# main.net
KiCad netlist of a schematic drawn in Altium Designer
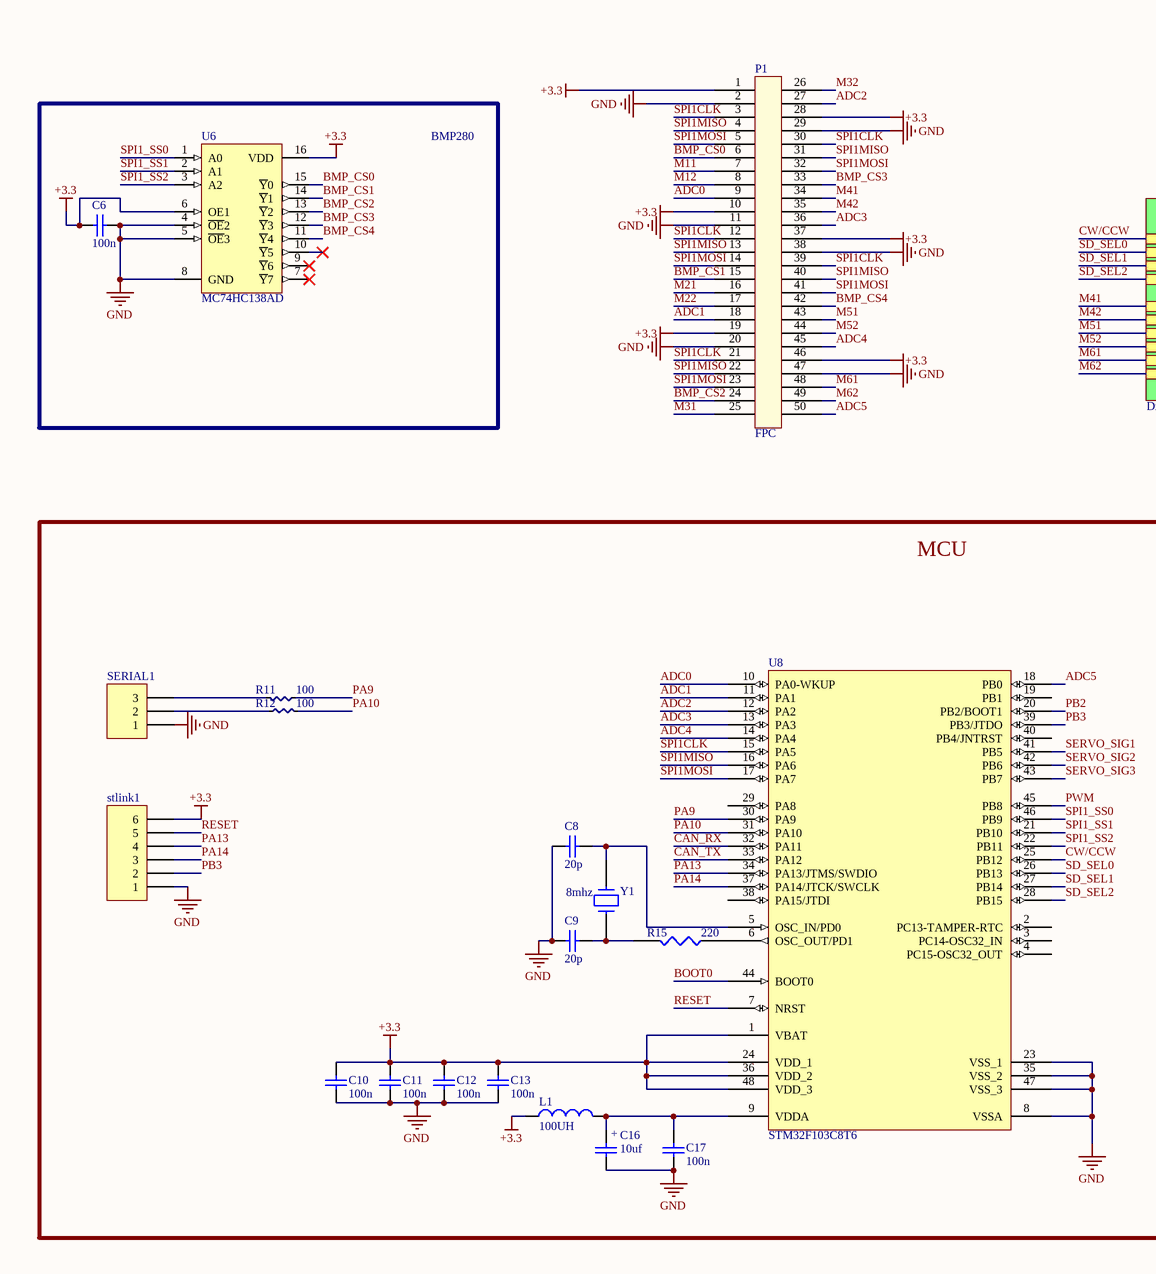
[diagram p0: main.SchDoc, left]
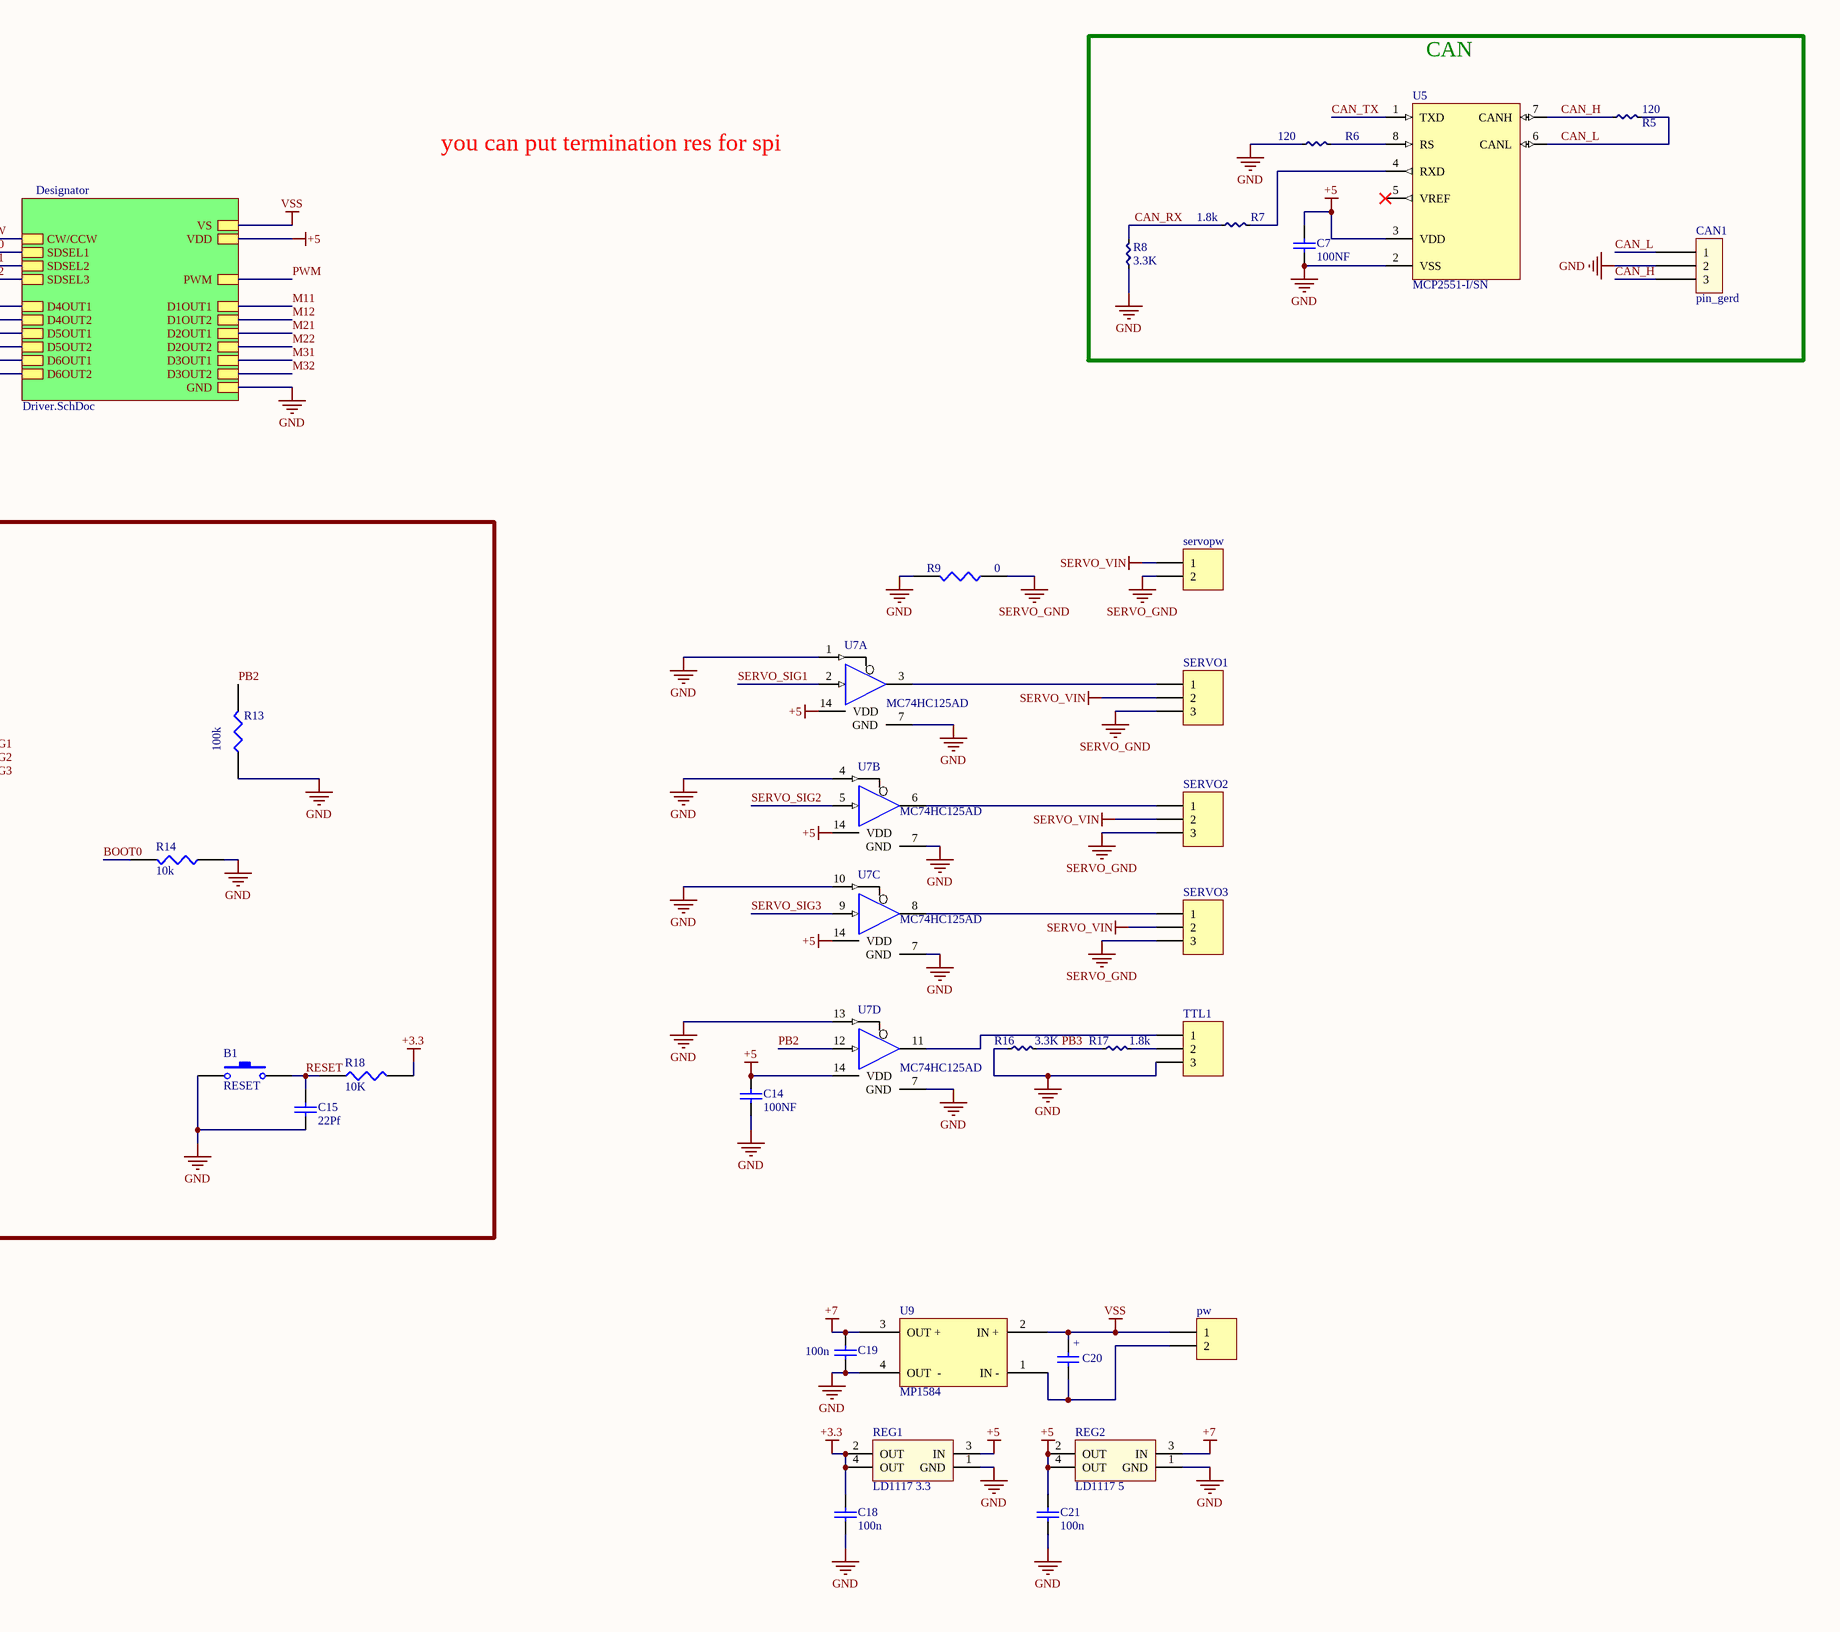
[diagram p1: main.SchDoc, right]

(export (version "E")
  (design (tool "Eeschema 10.0.6"))
  (components
    (comp (ref "B1")
      (value "RESET")
      (footprint "SMD PUSH BUTTON")
      (libsource (lib "AMINLIB") (part "SMD_PUSH_BUTTON"))
    )
    (comp (ref "C6")
      (value "100n")
      (footprint "MY_CAP_SMD_0805")
      (libsource (lib "AMINLIB") (part "CAP SMD"))
    )
    (comp (ref "C7")
      (value "100NF")
      (footprint "MY_CAP_SMD_0805")
      (description "2.0 mm × 1.25 mm")
      (libsource (lib "AMINLIB") (part "CAP SMD_0805"))
    )
    (comp (ref "C8") (value "20p") (footprint "MY_CAP_SMD_0805") (libsource (lib "AMINLIB") (part "CAP SMD")))
    (comp (ref "C9") (value "20p") (footprint "MY_CAP_SMD_0805") (libsource (lib "AMINLIB") (part "CAP SMD")))
    (comp (ref "C10")
      (value "100n")
      (footprint "MY_CAP_SMD_0805")
      (libsource (lib "AMINLIB") (part "CAP SMD"))
    )
    (comp (ref "C11")
      (value "100n")
      (footprint "MY_CAP_SMD_0805")
      (libsource (lib "AMINLIB") (part "CAP SMD"))
    )
    (comp (ref "C12")
      (value "100n")
      (footprint "MY_CAP_SMD_0805")
      (libsource (lib "AMINLIB") (part "CAP SMD"))
    )
    (comp (ref "C13")
      (value "100n")
      (footprint "MY_CAP_SMD_0805")
      (libsource (lib "AMINLIB") (part "CAP SMD"))
    )
    (comp (ref "C14")
      (value "100NF")
      (footprint "MY_CAP_SMD_0805")
      (description "2.0 mm × 1.25 mm")
      (libsource (lib "AMINLIB") (part "CAP SMD_0805"))
    )
    (comp (ref "C15")
      (value "22Pf")
      (footprint "MY_CAP_SMD_0805")
      (libsource (lib "AMINLIB") (part "CAP SMD"))
    )
    (comp (ref "C16")
      (value "10uf")
      (footprint "MY_cap_smd10uf")
      (libsource (lib "AMINLIB") (part "cap_smd_10u"))
    )
    (comp (ref "C17")
      (value "100n")
      (footprint "MY_CAP_SMD_0805")
      (libsource (lib "AMINLIB") (part "CAP SMD"))
    )
    (comp (ref "C18")
      (value "100n")
      (footprint "MY_CAP_SMD_0805")
      (libsource (lib "AMINLIB") (part "CAP SMD"))
    )
    (comp (ref "C19")
      (value "100n")
      (footprint "MY_CAP_SMD_0805")
      (libsource (lib "AMINLIB") (part "CAP SMD"))
    )
    (comp (ref "C20")
      (value "Cap")
      (footprint "MY_CAP_SMD-C")
      (description "6X3.2MM")
      (libsource (lib "AMINLIB") (part "CAP_TANTAL_C"))
    )
    (comp (ref "C21")
      (value "100n")
      (footprint "MY_CAP_SMD_0805")
      (libsource (lib "AMINLIB") (part "CAP SMD"))
    )
    (comp (ref "CAN1")
      (value "pin_gerd")
      (footprint "MY_PINGERD3")
      (description "3pin")
      (libsource (lib "AMINLIB") (part "pin_gerd"))
    )
    (comp (ref "L1")
      (value "100UH")
      (footprint "MY_SMD_INDUCTOR")
      (libsource (lib "AMINLIB") (part "INDUCTOR SMD"))
    )
    (comp (ref "P1")
      (value "FPC")
      (footprint "FPC-50-POS-0.5-MM")
      (libsource (lib "HAND-MULTILAYER") (part "FPC-50-POS-0.5-MM"))
    )
    (comp (ref "pw")
      (value "Header 2")
      (footprint "My_1X02")
      (description "Header, 2-Pin")
      (fields (field (name "PUBLISHER") "Altium Limited"))
      (libsource (lib "AMINLIB") (part "Header 2"))
    )
    (comp (ref "R5")
      (value "120")
      (footprint "MY_RES_SMD_0805")
      (libsource (lib "AMINLIB") (part "RES SMD 0805"))
    )
    (comp (ref "R6")
      (value "120")
      (footprint "MY_RES_SMD_0805")
      (libsource (lib "AMINLIB") (part "RES SMD 0805"))
    )
    (comp (ref "R7")
      (value "1.8k")
      (footprint "MY_RES_SMD_0805")
      (libsource (lib "AMINLIB") (part "RES SMD 0805"))
    )
    (comp (ref "R8")
      (value "3.3K")
      (footprint "MY_RES_SMD_0805")
      (libsource (lib "AMINLIB") (part "RES SMD 0805"))
    )
    (comp (ref "R9") (value "0") (footprint "MY_RES_SMD_0805") (libsource (lib "AMINLIB") (part "RES SMD")))
    (comp (ref "R11")
      (value "100")
      (footprint "MY_RES_SMD_0805")
      (libsource (lib "AMINLIB") (part "RES SMD 0805"))
    )
    (comp (ref "R12")
      (value "100")
      (footprint "MY_RES_SMD_0805")
      (libsource (lib "AMINLIB") (part "RES SMD 0805"))
    )
    (comp (ref "R13")
      (value "100k")
      (footprint "MY_RES_SMD_0805")
      (libsource (lib "AMINLIB") (part "RES SMD"))
    )
    (comp (ref "R14")
      (value "10k")
      (footprint "MY_RES_SMD_0805")
      (libsource (lib "AMINLIB") (part "RES SMD"))
    )
    (comp (ref "R15")
      (value "220")
      (footprint "MY_RES_SMD_0805")
      (libsource (lib "AMINLIB") (part "RES SMD"))
    )
    (comp (ref "R16")
      (value "3.3K")
      (footprint "MY_RES_SMD_0805")
      (libsource (lib "AMINLIB") (part "RES SMD 0805"))
    )
    (comp (ref "R17")
      (value "1.8k")
      (footprint "MY_RES_SMD_0805")
      (libsource (lib "AMINLIB") (part "RES SMD 0805"))
    )
    (comp (ref "R18")
      (value "10K")
      (footprint "MY_RES_SMD_0805")
      (libsource (lib "AMINLIB") (part "RES SMD"))
    )
    (comp (ref "REG1")
      (value "LD1117 3.3")
      (footprint "MY_LD1117-3.3")
      (libsource (lib "AMINLIB") (part "LD1117 3.3"))
    )
    (comp (ref "REG2")
      (value "LD1117 5")
      (footprint "MY_LD1117-3.3")
      (libsource (lib "AMINLIB") (part "LD1117 3.3"))
    )
    (comp (ref "SERIAL1")
      (value "Header 3")
      (footprint "My_1X03")
      (description "Header, 3-Pin")
      (fields (field (name "PUBLISHER") "Altium Limited"))
      (libsource (lib "") (part "Header 3_1"))
    )
    (comp (ref "SERVO1")
      (value "Header 3")
      (footprint "My_1X03")
      (description "Header, 3-Pin")
      (fields (field (name "PUBLISHER") "Altium Limited"))
      (libsource (lib "AMINLIB") (part "Header 3"))
    )
    (comp (ref "SERVO2")
      (value "Header 3")
      (footprint "My_1X03")
      (description "Header, 3-Pin")
      (fields (field (name "PUBLISHER") "Altium Limited"))
      (libsource (lib "AMINLIB") (part "Header 3"))
    )
    (comp (ref "SERVO3")
      (value "Header 3")
      (footprint "My_1X03")
      (description "Header, 3-Pin")
      (fields (field (name "PUBLISHER") "Altium Limited"))
      (libsource (lib "AMINLIB") (part "Header 3"))
    )
    (comp (ref "servopw")
      (value "Header 2")
      (footprint "My_1X02")
      (description "Header, 2-Pin")
      (fields (field (name "PUBLISHER") "Altium Limited"))
      (libsource (lib "AMINLIB") (part "Header 2"))
    )
    (comp (ref "stlink1")
      (value "Header 6")
      (footprint "My_1X06")
      (description "Header, 6-Pin")
      (fields (field (name "PUBLISHER") "Altium Limited"))
      (libsource (lib "AMINLIB") (part "Header 6"))
    )
    (comp (ref "TTL1")
      (value "Header 3")
      (footprint "My_1X03")
      (description "Header, 3-Pin")
      (fields (field (name "PUBLISHER") "Altium Limited"))
      (libsource (lib "AMINLIB") (part "Header 3"))
    )
    (comp (ref "U5")
      (value "MCP2551-I/SN")
      (footprint "SOIC-SN8_N")
      (description "High-Speed CAN Transceiver, 8-Pin SOIC, Industrial Temperature")
      (fields (field (name "PUBLISHER") "Altium Limited"))
      (libsource (lib "Microchip Interface") (part "MCP2551-I/SN"))
    )
    (comp (ref "U6")
      (value "MC74HC138AD")
      (footprint "751B-03_N")
      (description "1-of-8 Decoder/Demultiplexer")
      (fields (field (name "PUBLISHER") "Altium Limited"))
      (libsource (lib "Motorola Logic Decoder Demux") (part "MC74HC138AD"))
    )
    (comp (ref "U7")
      (value "MC74HC125AD")
      (footprint "751A-02_N")
      (description "Quad 3-State Non-Inverting Buffer")
      (fields (field (name "PUBLISHER") "Altium Limited"))
      (libsource (lib "Motorola Logic Buffer Line Driver") (part "MC74HC125AD"))
    )
    (comp (ref "U8")
      (value "STM32F103C8T6")
      (footprint "LQFP48_N")
      (description "STM32 ARM-based 32-bit MCU with 64 Kbytes Flash, 48-pin LQFP, Industrial Temperature")
      (fields (field (name "PUBLISHER") "Altium Limited"))
      (libsource (lib "ST Microcontroller 32-Bit STM32") (part "STM32F103C8T6"))
    )
    (comp (ref "U9")
      (value "MP1584")
      (footprint "mp1584")
      (description "SWITCHING REGULATOR MODULE")
      (fields (field (name "PART") "MP1584EN-LF-Z"))
      (libsource (lib "AMINLIB") (part "MP1584"))
    )
    (comp (ref "Y1")
      (value "8mhz")
      (footprint "My_Crystal - SMD")
      (description "Crystal")
      (libsource (lib "AMINLIB") (part "CRYSTAL"))
    )
  )
  (nets
    (net (code "1") (name "+3.3") (class "Default")
      (node (ref "C10") (pin "2") (pinfunction "2_2") (pintype "passive"))
      (node (ref "C11") (pin "2") (pinfunction "2_2") (pintype "passive"))
      (node (ref "C12") (pin "2") (pinfunction "2_2") (pintype "passive"))
      (node (ref "C13") (pin "2") (pinfunction "2_2") (pintype "passive"))
      (node (ref "C18") (pin "2") (pinfunction "2_2") (pintype "passive"))
      (node (ref "C6") (pin "2") (pinfunction "2_2") (pintype "passive"))
      (node (ref "L1") (pin "1") (pinfunction "1_1") (pintype "passive"))
      (node (ref "P1") (pin "1") (pinfunction "1_1") (pintype "passive"))
      (node (ref "P1") (pin "10") (pinfunction "10_10") (pintype "passive"))
      (node (ref "P1") (pin "19") (pinfunction "19_19") (pintype "passive"))
      (node (ref "P1") (pin "28") (pinfunction "28_28") (pintype "passive"))
      (node (ref "P1") (pin "37") (pinfunction "37_37") (pintype "passive"))
      (node (ref "P1") (pin "46") (pinfunction "46_46") (pintype "passive"))
      (node (ref "R18") (pin "2") (pinfunction "2_2") (pintype "passive"))
      (node (ref "REG1") (pin "2") (pinfunction "OUT_2") (pintype "power_in"))
      (node (ref "REG1") (pin "4") (pinfunction "OUT_4") (pintype "power_in"))
      (node (ref "U6") (pin "16") (pinfunction "VDD_16") (pintype "power_in"))
      (node (ref "U6") (pin "6") (pinfunction "OE1_6") (pintype "input"))
      (node (ref "U8") (pin "1") (pinfunction "VBAT_1") (pintype "power_in"))
      (node (ref "U8") (pin "24") (pinfunction "VDD_1_24") (pintype "power_in"))
      (node (ref "U8") (pin "36") (pinfunction "VDD_2_36") (pintype "power_in"))
      (node (ref "U8") (pin "48") (pinfunction "VDD_3_48") (pintype "power_in"))
      (node (ref "stlink1") (pin "6") (pinfunction "6_6") (pintype "passive"))
    )
    (net (code "2") (name "+5") (class "Default")
      (node (ref "C14") (pin "2") (pinfunction "2_2") (pintype "passive"))
      (node (ref "C21") (pin "2") (pinfunction "2_2") (pintype "passive"))
      (node (ref "C7") (pin "2") (pinfunction "2_2") (pintype "passive"))
      (node (ref "REG1") (pin "3") (pinfunction "IN_3") (pintype "power_in"))
      (node (ref "REG2") (pin "2") (pinfunction "OUT_2") (pintype "power_in"))
      (node (ref "REG2") (pin "4") (pinfunction "OUT_4") (pintype "power_in"))
      (node (ref "U5") (pin "3") (pinfunction "VDD_3") (pintype "power_in"))
      (node (ref "U7") (pin "14") (pinfunction "VDD_14") (pintype "power_in"))
    )
    (net (code "3") (name "+7") (class "Default")
      (node (ref "C19") (pin "2") (pinfunction "2_2") (pintype "passive"))
      (node (ref "REG2") (pin "3") (pinfunction "IN_3") (pintype "power_in"))
      (node (ref "U9") (pin "3") (pinfunction "OUT_+_3") (pintype "passive"))
    )
    (net (code "4") (name "/ADC0") (class "Default")
      (node (ref "P1") (pin "9") (pinfunction "9_9") (pintype "passive"))
      (node (ref "U8") (pin "10") (pinfunction "PA0-WKUP_10") (pintype "bidirectional"))
    )
    (net (code "5") (name "/ADC1") (class "Default")
      (node (ref "P1") (pin "18") (pinfunction "18_18") (pintype "passive"))
      (node (ref "U8") (pin "11") (pinfunction "PA1_11") (pintype "bidirectional"))
    )
    (net (code "6") (name "/ADC2") (class "Default")
      (node (ref "P1") (pin "27") (pinfunction "27_27") (pintype "passive"))
      (node (ref "U8") (pin "12") (pinfunction "PA2_12") (pintype "bidirectional"))
    )
    (net (code "7") (name "/ADC3") (class "Default")
      (node (ref "P1") (pin "36") (pinfunction "36_36") (pintype "passive"))
      (node (ref "U8") (pin "13") (pinfunction "PA3_13") (pintype "bidirectional"))
    )
    (net (code "8") (name "/ADC4") (class "Default")
      (node (ref "P1") (pin "45") (pinfunction "45_45") (pintype "passive"))
      (node (ref "U8") (pin "14") (pinfunction "PA4_14") (pintype "bidirectional"))
    )
    (net (code "9") (name "/ADC5") (class "Default")
      (node (ref "P1") (pin "50") (pinfunction "50_50") (pintype "passive"))
      (node (ref "U8") (pin "18") (pinfunction "PB0_18") (pintype "bidirectional"))
    )
    (net (code "10") (name "/BMP_CS0") (class "Default")
      (node (ref "P1") (pin "6") (pinfunction "6_6") (pintype "passive"))
      (node (ref "U6") (pin "15") (pinfunction "~{Y}0_15") (pintype "output"))
    )
    (net (code "11") (name "/BMP_CS1") (class "Default")
      (node (ref "P1") (pin "15") (pinfunction "15_15") (pintype "passive"))
      (node (ref "U6") (pin "14") (pinfunction "~{Y}1_14") (pintype "output"))
    )
    (net (code "12") (name "/BMP_CS2") (class "Default")
      (node (ref "P1") (pin "24") (pinfunction "24_24") (pintype "passive"))
      (node (ref "U6") (pin "13") (pinfunction "~{Y}2_13") (pintype "output"))
    )
    (net (code "13") (name "/BMP_CS3") (class "Default")
      (node (ref "P1") (pin "33") (pinfunction "33_33") (pintype "passive"))
      (node (ref "U6") (pin "12") (pinfunction "~{Y}3_12") (pintype "output"))
    )
    (net (code "14") (name "/BMP_CS4") (class "Default")
      (node (ref "P1") (pin "42") (pinfunction "42_42") (pintype "passive"))
      (node (ref "U6") (pin "11") (pinfunction "~{Y}4_11") (pintype "output"))
    )
    (net (code "15") (name "/BOOT0") (class "Default")
      (node (ref "R14") (pin "2") (pinfunction "2_2") (pintype "passive"))
      (node (ref "U8") (pin "44") (pinfunction "BOOT0_44") (pintype "input"))
    )
    (net (code "16") (name "/CAN_H") (class "Default")
      (node (ref "CAN1") (pin "3") (pinfunction "3_3") (pintype "passive"))
      (node (ref "R5") (pin "1") (pinfunction "1_1") (pintype "passive"))
      (node (ref "U5") (pin "7") (pinfunction "CANH_7") (pintype "bidirectional"))
    )
    (net (code "17") (name "/CAN_L") (class "Default")
      (node (ref "CAN1") (pin "1") (pinfunction "1_1") (pintype "passive"))
      (node (ref "R5") (pin "2") (pinfunction "2_2") (pintype "passive"))
      (node (ref "U5") (pin "6") (pinfunction "CANL_6") (pintype "bidirectional"))
    )
    (net (code "18") (name "/CAN_RX") (class "Default")
      (node (ref "R7") (pin "1") (pinfunction "1_1") (pintype "passive"))
      (node (ref "R8") (pin "2") (pinfunction "2_2") (pintype "passive"))
      (node (ref "U8") (pin "32") (pinfunction "PA11_32") (pintype "bidirectional"))
    )
    (net (code "19") (name "/CAN_TX") (class "Default")
      (node (ref "U5") (pin "1") (pinfunction "TXD_1") (pintype "input"))
      (node (ref "U8") (pin "33") (pinfunction "PA12_33") (pintype "bidirectional"))
    )
    (net (code "20") (name "/CW{slash}CCW") (class "Default")
      (node (ref "U8") (pin "25") (pinfunction "PB12_25") (pintype "bidirectional"))
    )
    (net (code "21") (name "/M11") (class "Default")
      (node (ref "P1") (pin "7") (pinfunction "7_7") (pintype "passive"))
    )
    (net (code "22") (name "/M12") (class "Default")
      (node (ref "P1") (pin "8") (pinfunction "8_8") (pintype "passive"))
    )
    (net (code "23") (name "/M21") (class "Default")
      (node (ref "P1") (pin "16") (pinfunction "16_16") (pintype "passive"))
    )
    (net (code "24") (name "/M22") (class "Default")
      (node (ref "P1") (pin "17") (pinfunction "17_17") (pintype "passive"))
    )
    (net (code "25") (name "/M31") (class "Default")
      (node (ref "P1") (pin "25") (pinfunction "25_25") (pintype "passive"))
    )
    (net (code "26") (name "/M32") (class "Default")
      (node (ref "P1") (pin "26") (pinfunction "26_26") (pintype "passive"))
    )
    (net (code "27") (name "/M41") (class "Default")
      (node (ref "P1") (pin "34") (pinfunction "34_34") (pintype "passive"))
    )
    (net (code "28") (name "/M42") (class "Default")
      (node (ref "P1") (pin "35") (pinfunction "35_35") (pintype "passive"))
    )
    (net (code "29") (name "/M51") (class "Default")
      (node (ref "P1") (pin "43") (pinfunction "43_43") (pintype "passive"))
    )
    (net (code "30") (name "/M52") (class "Default")
      (node (ref "P1") (pin "44") (pinfunction "44_44") (pintype "passive"))
    )
    (net (code "31") (name "/M61") (class "Default")
      (node (ref "P1") (pin "48") (pinfunction "48_48") (pintype "passive"))
    )
    (net (code "32") (name "/M62") (class "Default")
      (node (ref "P1") (pin "49") (pinfunction "49_49") (pintype "passive"))
    )
    (net (code "33") (name "/PA9") (class "Default")
      (node (ref "R11") (pin "1") (pinfunction "1_1") (pintype "passive"))
      (node (ref "U8") (pin "30") (pinfunction "PA9_30") (pintype "bidirectional"))
    )
    (net (code "34") (name "/PA10") (class "Default")
      (node (ref "R12") (pin "2") (pinfunction "2_2") (pintype "passive"))
      (node (ref "U8") (pin "31") (pinfunction "PA10_31") (pintype "bidirectional"))
    )
    (net (code "35") (name "/PA13") (class "Default")
      (node (ref "U8") (pin "34") (pinfunction "PA13/JTMS/SWDIO_34") (pintype "bidirectional"))
      (node (ref "stlink1") (pin "4") (pinfunction "4_4") (pintype "passive"))
    )
    (net (code "36") (name "/PA14") (class "Default")
      (node (ref "U8") (pin "37") (pinfunction "PA14/JTCK/SWCLK_37") (pintype "bidirectional"))
      (node (ref "stlink1") (pin "3") (pinfunction "3_3") (pintype "passive"))
    )
    (net (code "37") (name "/PB2") (class "Default")
      (node (ref "R13") (pin "2") (pinfunction "2_2") (pintype "passive"))
      (node (ref "U7") (pin "12") (pinfunction "A_12") (pintype "input"))
      (node (ref "U8") (pin "20") (pinfunction "PB2/BOOT1_20") (pintype "bidirectional"))
    )
    (net (code "38") (name "/PB3") (class "Default")
      (node (ref "R16") (pin "2") (pinfunction "2_2") (pintype "passive"))
      (node (ref "R17") (pin "1") (pinfunction "1_1") (pintype "passive"))
      (node (ref "U8") (pin "39") (pinfunction "PB3/JTDO_39") (pintype "bidirectional"))
      (node (ref "stlink1") (pin "2") (pinfunction "2_2") (pintype "passive"))
    )
    (net (code "39") (name "/PWM") (class "Default")
      (node (ref "U8") (pin "45") (pinfunction "PB8_45") (pintype "bidirectional"))
    )
    (net (code "40") (name "/RESET") (class "Default")
      (node (ref "B1") (pin "2") (pinfunction "2_2") (pintype "passive"))
      (node (ref "C15") (pin "2") (pinfunction "2_2") (pintype "passive"))
      (node (ref "R18") (pin "1") (pinfunction "1_1") (pintype "passive"))
      (node (ref "U8") (pin "7") (pinfunction "NRST_7") (pintype "bidirectional"))
      (node (ref "stlink1") (pin "5") (pinfunction "5_5") (pintype "passive"))
    )
    (net (code "41") (name "/SD_SEL0") (class "Default")
      (node (ref "U8") (pin "26") (pinfunction "PB13_26") (pintype "bidirectional"))
    )
    (net (code "42") (name "/SD_SEL1") (class "Default")
      (node (ref "U8") (pin "27") (pinfunction "PB14_27") (pintype "bidirectional"))
    )
    (net (code "43") (name "/SD_SEL2") (class "Default")
      (node (ref "U8") (pin "28") (pinfunction "PB15_28") (pintype "bidirectional"))
    )
    (net (code "44") (name "/SERVO_SIG1") (class "Default")
      (node (ref "U7") (pin "2") (pinfunction "A_2") (pintype "input"))
      (node (ref "U8") (pin "41") (pinfunction "PB5_41") (pintype "bidirectional"))
    )
    (net (code "45") (name "/SERVO_SIG2") (class "Default")
      (node (ref "U7") (pin "5") (pinfunction "A_5") (pintype "input"))
      (node (ref "U8") (pin "42") (pinfunction "PB6_42") (pintype "bidirectional"))
    )
    (net (code "46") (name "/SERVO_SIG3") (class "Default")
      (node (ref "U7") (pin "9") (pinfunction "A_9") (pintype "input"))
      (node (ref "U8") (pin "43") (pinfunction "PB7_43") (pintype "bidirectional"))
    )
    (net (code "47") (name "/SPI1CLK") (class "Default")
      (node (ref "P1") (pin "12") (pinfunction "12_12") (pintype "passive"))
      (node (ref "P1") (pin "21") (pinfunction "21_21") (pintype "passive"))
      (node (ref "P1") (pin "3") (pinfunction "3_3") (pintype "passive"))
      (node (ref "P1") (pin "30") (pinfunction "30_30") (pintype "passive"))
      (node (ref "P1") (pin "39") (pinfunction "39_39") (pintype "passive"))
      (node (ref "U8") (pin "15") (pinfunction "PA5_15") (pintype "bidirectional"))
    )
    (net (code "48") (name "/SPI1MISO") (class "Default")
      (node (ref "P1") (pin "13") (pinfunction "13_13") (pintype "passive"))
      (node (ref "P1") (pin "22") (pinfunction "22_22") (pintype "passive"))
      (node (ref "P1") (pin "31") (pinfunction "31_31") (pintype "passive"))
      (node (ref "P1") (pin "4") (pinfunction "4_4") (pintype "passive"))
      (node (ref "P1") (pin "40") (pinfunction "40_40") (pintype "passive"))
      (node (ref "U8") (pin "16") (pinfunction "PA6_16") (pintype "bidirectional"))
    )
    (net (code "49") (name "/SPI1MOSI") (class "Default")
      (node (ref "P1") (pin "14") (pinfunction "14_14") (pintype "passive"))
      (node (ref "P1") (pin "23") (pinfunction "23_23") (pintype "passive"))
      (node (ref "P1") (pin "32") (pinfunction "32_32") (pintype "passive"))
      (node (ref "P1") (pin "41") (pinfunction "41_41") (pintype "passive"))
      (node (ref "P1") (pin "5") (pinfunction "5_5") (pintype "passive"))
      (node (ref "U8") (pin "17") (pinfunction "PA7_17") (pintype "bidirectional"))
    )
    (net (code "50") (name "/SPI1_SS0") (class "Default")
      (node (ref "U6") (pin "1") (pinfunction "A0_1") (pintype "input"))
      (node (ref "U8") (pin "46") (pinfunction "PB9_46") (pintype "bidirectional"))
    )
    (net (code "51") (name "/SPI1_SS1") (class "Default")
      (node (ref "U6") (pin "2") (pinfunction "A1_2") (pintype "input"))
      (node (ref "U8") (pin "21") (pinfunction "PB10_21") (pintype "bidirectional"))
    )
    (net (code "52") (name "/SPI1_SS2") (class "Default")
      (node (ref "U6") (pin "3") (pinfunction "A2_3") (pintype "input"))
      (node (ref "U8") (pin "22") (pinfunction "PB11_22") (pintype "bidirectional"))
    )
    (net (code "53") (name "GND") (class "Default")
      (node (ref "B1") (pin "1") (pinfunction "1_1") (pintype "passive"))
      (node (ref "C10") (pin "1") (pinfunction "1_1") (pintype "passive"))
      (node (ref "C11") (pin "1") (pinfunction "1_1") (pintype "passive"))
      (node (ref "C12") (pin "1") (pinfunction "1_1") (pintype "passive"))
      (node (ref "C13") (pin "1") (pinfunction "1_1") (pintype "passive"))
      (node (ref "C14") (pin "1") (pinfunction "1_1") (pintype "passive"))
      (node (ref "C15") (pin "1") (pinfunction "1_1") (pintype "passive"))
      (node (ref "C16") (pin "-") (pinfunction "-_-") (pintype "passive"))
      (node (ref "C17") (pin "1") (pinfunction "1_1") (pintype "passive"))
      (node (ref "C18") (pin "1") (pinfunction "1_1") (pintype "passive"))
      (node (ref "C19") (pin "1") (pinfunction "1_1") (pintype "passive"))
      (node (ref "C21") (pin "1") (pinfunction "1_1") (pintype "passive"))
      (node (ref "C6") (pin "1") (pinfunction "1_1") (pintype "passive"))
      (node (ref "C7") (pin "1") (pinfunction "1_1") (pintype "passive"))
      (node (ref "C8") (pin "2") (pinfunction "2_2") (pintype "passive"))
      (node (ref "C9") (pin "1") (pinfunction "1_1") (pintype "passive"))
      (node (ref "CAN1") (pin "2") (pinfunction "2_2") (pintype "passive"))
      (node (ref "P1") (pin "11") (pinfunction "11_11") (pintype "passive"))
      (node (ref "P1") (pin "2") (pinfunction "2_2") (pintype "passive"))
      (node (ref "P1") (pin "20") (pinfunction "20_20") (pintype "passive"))
      (node (ref "P1") (pin "29") (pinfunction "29_29") (pintype "passive"))
      (node (ref "P1") (pin "38") (pinfunction "38_38") (pintype "passive"))
      (node (ref "P1") (pin "47") (pinfunction "47_47") (pintype "passive"))
      (node (ref "R13") (pin "1") (pinfunction "1_1") (pintype "passive"))
      (node (ref "R14") (pin "1") (pinfunction "1_1") (pintype "passive"))
      (node (ref "R16") (pin "1") (pinfunction "1_1") (pintype "passive"))
      (node (ref "R6") (pin "1") (pinfunction "1_1") (pintype "passive"))
      (node (ref "R8") (pin "1") (pinfunction "1_1") (pintype "passive"))
      (node (ref "R9") (pin "2") (pinfunction "2_2") (pintype "passive"))
      (node (ref "REG1") (pin "1") (pinfunction "GND_1") (pintype "power_in"))
      (node (ref "REG2") (pin "1") (pinfunction "GND_1") (pintype "power_in"))
      (node (ref "SERIAL1") (pin "1") (pinfunction "1_1") (pintype "passive"))
      (node (ref "TTL1") (pin "3") (pinfunction "3_3") (pintype "passive"))
      (node (ref "U5") (pin "2") (pinfunction "VSS_2") (pintype "power_in"))
      (node (ref "U6") (pin "4") (pinfunction "~{OE}2_4") (pintype "input"))
      (node (ref "U6") (pin "5") (pinfunction "~{OE}3_5") (pintype "input"))
      (node (ref "U6") (pin "8") (pinfunction "GND_8") (pintype "power_in"))
      (node (ref "U7") (pin "1") (pinfunction "~{OE}_1") (pintype "input"))
      (node (ref "U7") (pin "10") (pinfunction "~{OE}_10") (pintype "input"))
      (node (ref "U7") (pin "13") (pinfunction "~{OE}_13") (pintype "input"))
      (node (ref "U7") (pin "4") (pinfunction "~{OE}_4") (pintype "input"))
      (node (ref "U7") (pin "7") (pinfunction "GND_7") (pintype "power_in"))
      (node (ref "U8") (pin "23") (pinfunction "VSS_1_23") (pintype "power_in"))
      (node (ref "U8") (pin "35") (pinfunction "VSS_2_35") (pintype "power_in"))
      (node (ref "U8") (pin "47") (pinfunction "VSS_3_47") (pintype "power_in"))
      (node (ref "U8") (pin "8") (pinfunction "VSSA_8") (pintype "power_in"))
      (node (ref "U9") (pin "4") (pinfunction "OUT__-_4") (pintype "passive"))
      (node (ref "stlink1") (pin "1") (pinfunction "1_1") (pintype "passive"))
    )
    (net (code "54") (name "Net-(C9-Pad2)") (class "Default")
      (node (ref "C9") (pin "2") (pinfunction "2_2") (pintype "passive"))
      (node (ref "R15") (pin "2") (pinfunction "2_2") (pintype "passive"))
      (node (ref "Y1") (pin "1") (pinfunction "1_1") (pintype "passive"))
    )
    (net (code "55") (name "Net-(R11-Pad2)") (class "Default")
      (node (ref "R11") (pin "2") (pinfunction "2_2") (pintype "passive"))
      (node (ref "SERIAL1") (pin "3") (pinfunction "3_3") (pintype "passive"))
    )
    (net (code "56") (name "Net-(R12-Pad1)") (class "Default")
      (node (ref "R12") (pin "1") (pinfunction "1_1") (pintype "passive"))
      (node (ref "SERIAL1") (pin "2") (pinfunction "2_2") (pintype "passive"))
    )
    (net (code "57") (name "Net-(R17-Pad2)") (class "Default")
      (node (ref "R17") (pin "2") (pinfunction "2_2") (pintype "passive"))
      (node (ref "TTL1") (pin "2") (pinfunction "2_2") (pintype "passive"))
    )
    (net (code "58") (name "Net-(U5-RS)") (class "Default")
      (node (ref "R6") (pin "2") (pinfunction "2_2") (pintype "passive"))
      (node (ref "U5") (pin "8") (pinfunction "RS_8") (pintype "input"))
    )
    (net (code "59") (name "Net-(U5-RXD)") (class "Default")
      (node (ref "R7") (pin "2") (pinfunction "2_2") (pintype "passive"))
      (node (ref "U5") (pin "4") (pinfunction "RXD_4") (pintype "output"))
    )
    (net (code "60") (name "Net-(U7A-Y)") (class "Default")
      (node (ref "SERVO1") (pin "1") (pinfunction "1_1") (pintype "passive"))
      (node (ref "U7") (pin "3") (pinfunction "Y_3") (pintype "tri_state"))
    )
    (net (code "61") (name "Net-(U7B-Y)") (class "Default")
      (node (ref "SERVO2") (pin "1") (pinfunction "1_1") (pintype "passive"))
      (node (ref "U7") (pin "6") (pinfunction "Y_6") (pintype "tri_state"))
    )
    (net (code "62") (name "Net-(U7C-Y)") (class "Default")
      (node (ref "SERVO3") (pin "1") (pinfunction "1_1") (pintype "passive"))
      (node (ref "U7") (pin "8") (pinfunction "Y_8") (pintype "tri_state"))
    )
    (net (code "63") (name "Net-(U7D-Y)") (class "Default")
      (node (ref "TTL1") (pin "1") (pinfunction "1_1") (pintype "passive"))
      (node (ref "U7") (pin "11") (pinfunction "Y_11") (pintype "tri_state"))
    )
    (net (code "64") (name "Net-(U8-OSC_IN{slash}PD0)") (class "Default")
      (node (ref "C8") (pin "1") (pinfunction "1_1") (pintype "passive"))
      (node (ref "U8") (pin "5") (pinfunction "OSC_IN/PD0_5") (pintype "input"))
      (node (ref "Y1") (pin "2") (pinfunction "2_2") (pintype "passive"))
    )
    (net (code "65") (name "Net-(U8-OSC_OUT{slash}PD1)") (class "Default")
      (node (ref "R15") (pin "1") (pinfunction "1_1") (pintype "passive"))
      (node (ref "U8") (pin "6") (pinfunction "OSC_OUT/PD1_6") (pintype "output"))
    )
    (net (code "66") (name "Net-(U8-VDDA)") (class "Default")
      (node (ref "C16") (pin "+") (pinfunction "+_+") (pintype "passive"))
      (node (ref "C17") (pin "2") (pinfunction "2_2") (pintype "passive"))
      (node (ref "L1") (pin "2") (pinfunction "2_2") (pintype "passive"))
      (node (ref "U8") (pin "9") (pinfunction "VDDA_9") (pintype "power_in"))
    )
    (net (code "67") (name "Net-(U9-IN_-)") (class "Default")
      (node (ref "C20") (pin "-") (pinfunction "-_-") (pintype "passive"))
      (node (ref "U9") (pin "1") (pinfunction "IN_-_1") (pintype "passive"))
      (node (ref "pw") (pin "2") (pinfunction "2_2") (pintype "passive"))
    )
    (net (code "68") (name "SERVO_GND") (class "Default")
      (node (ref "R9") (pin "1") (pinfunction "1_1") (pintype "passive"))
      (node (ref "SERVO1") (pin "3") (pinfunction "3_3") (pintype "passive"))
      (node (ref "SERVO2") (pin "3") (pinfunction "3_3") (pintype "passive"))
      (node (ref "SERVO3") (pin "3") (pinfunction "3_3") (pintype "passive"))
      (node (ref "servopw") (pin "2") (pinfunction "2_2") (pintype "passive"))
    )
    (net (code "69") (name "SERVO_VIN") (class "Default")
      (node (ref "SERVO1") (pin "2") (pinfunction "2_2") (pintype "passive"))
      (node (ref "SERVO2") (pin "2") (pinfunction "2_2") (pintype "passive"))
      (node (ref "SERVO3") (pin "2") (pinfunction "2_2") (pintype "passive"))
      (node (ref "servopw") (pin "1") (pinfunction "1_1") (pintype "passive"))
    )
    (net (code "70") (name "VSS") (class "Default")
      (node (ref "C20") (pin "+") (pinfunction "+_+") (pintype "passive"))
      (node (ref "U9") (pin "2") (pinfunction "IN_+_2") (pintype "passive"))
      (node (ref "pw") (pin "1") (pinfunction "1_1") (pintype "passive"))
    )
    (net (code "71") (name "unconnected-(U5-VREF-Pad5)") (class "Default")
      (node (ref "U5") (pin "5") (pinfunction "VREF_5") (pintype "output+no_connect"))
    )
    (net (code "72") (name "unconnected-(U6-~{Y}5-Pad10)") (class "Default")
      (node (ref "U6") (pin "10") (pinfunction "~{Y}5_10") (pintype "output+no_connect"))
    )
    (net (code "73") (name "unconnected-(U6-~{Y}6-Pad9)") (class "Default")
      (node (ref "U6") (pin "9") (pinfunction "~{Y}6_9") (pintype "output+no_connect"))
    )
    (net (code "74") (name "unconnected-(U6-~{Y}7-Pad7)") (class "Default")
      (node (ref "U6") (pin "7") (pinfunction "~{Y}7_7") (pintype "output+no_connect"))
    )
    (net (code "75") (name "unconnected-(U8-PA8-Pad29)") (class "Default")
      (node (ref "U8") (pin "29") (pinfunction "PA8_29") (pintype "bidirectional"))
    )
    (net (code "76") (name "unconnected-(U8-PA15{slash}JTDI-Pad38)") (class "Default")
      (node (ref "U8") (pin "38") (pinfunction "PA15/JTDI_38") (pintype "bidirectional"))
    )
    (net (code "77") (name "unconnected-(U8-PB1-Pad19)") (class "Default")
      (node (ref "U8") (pin "19") (pinfunction "PB1_19") (pintype "bidirectional"))
    )
    (net (code "78") (name "unconnected-(U8-PB4{slash}JNTRST-Pad40)") (class "Default")
      (node (ref "U8") (pin "40") (pinfunction "PB4/JNTRST_40") (pintype "bidirectional"))
    )
    (net (code "79") (name "unconnected-(U8-PC13-TAMPER-RTC-Pad2)") (class "Default")
      (node (ref "U8") (pin "2") (pinfunction "PC13-TAMPER-RTC_2") (pintype "bidirectional"))
    )
    (net (code "80") (name "unconnected-(U8-PC14-OSC32_IN-Pad3)") (class "Default")
      (node (ref "U8") (pin "3") (pinfunction "PC14-OSC32_IN_3") (pintype "bidirectional"))
    )
    (net (code "81") (name "unconnected-(U8-PC15-OSC32_OUT-Pad4)") (class "Default")
      (node (ref "U8") (pin "4") (pinfunction "PC15-OSC32_OUT_4") (pintype "bidirectional"))
    )
  )
)
